# basic-HR20.net
KiCad netlist of a schematic drawn in EAGLE
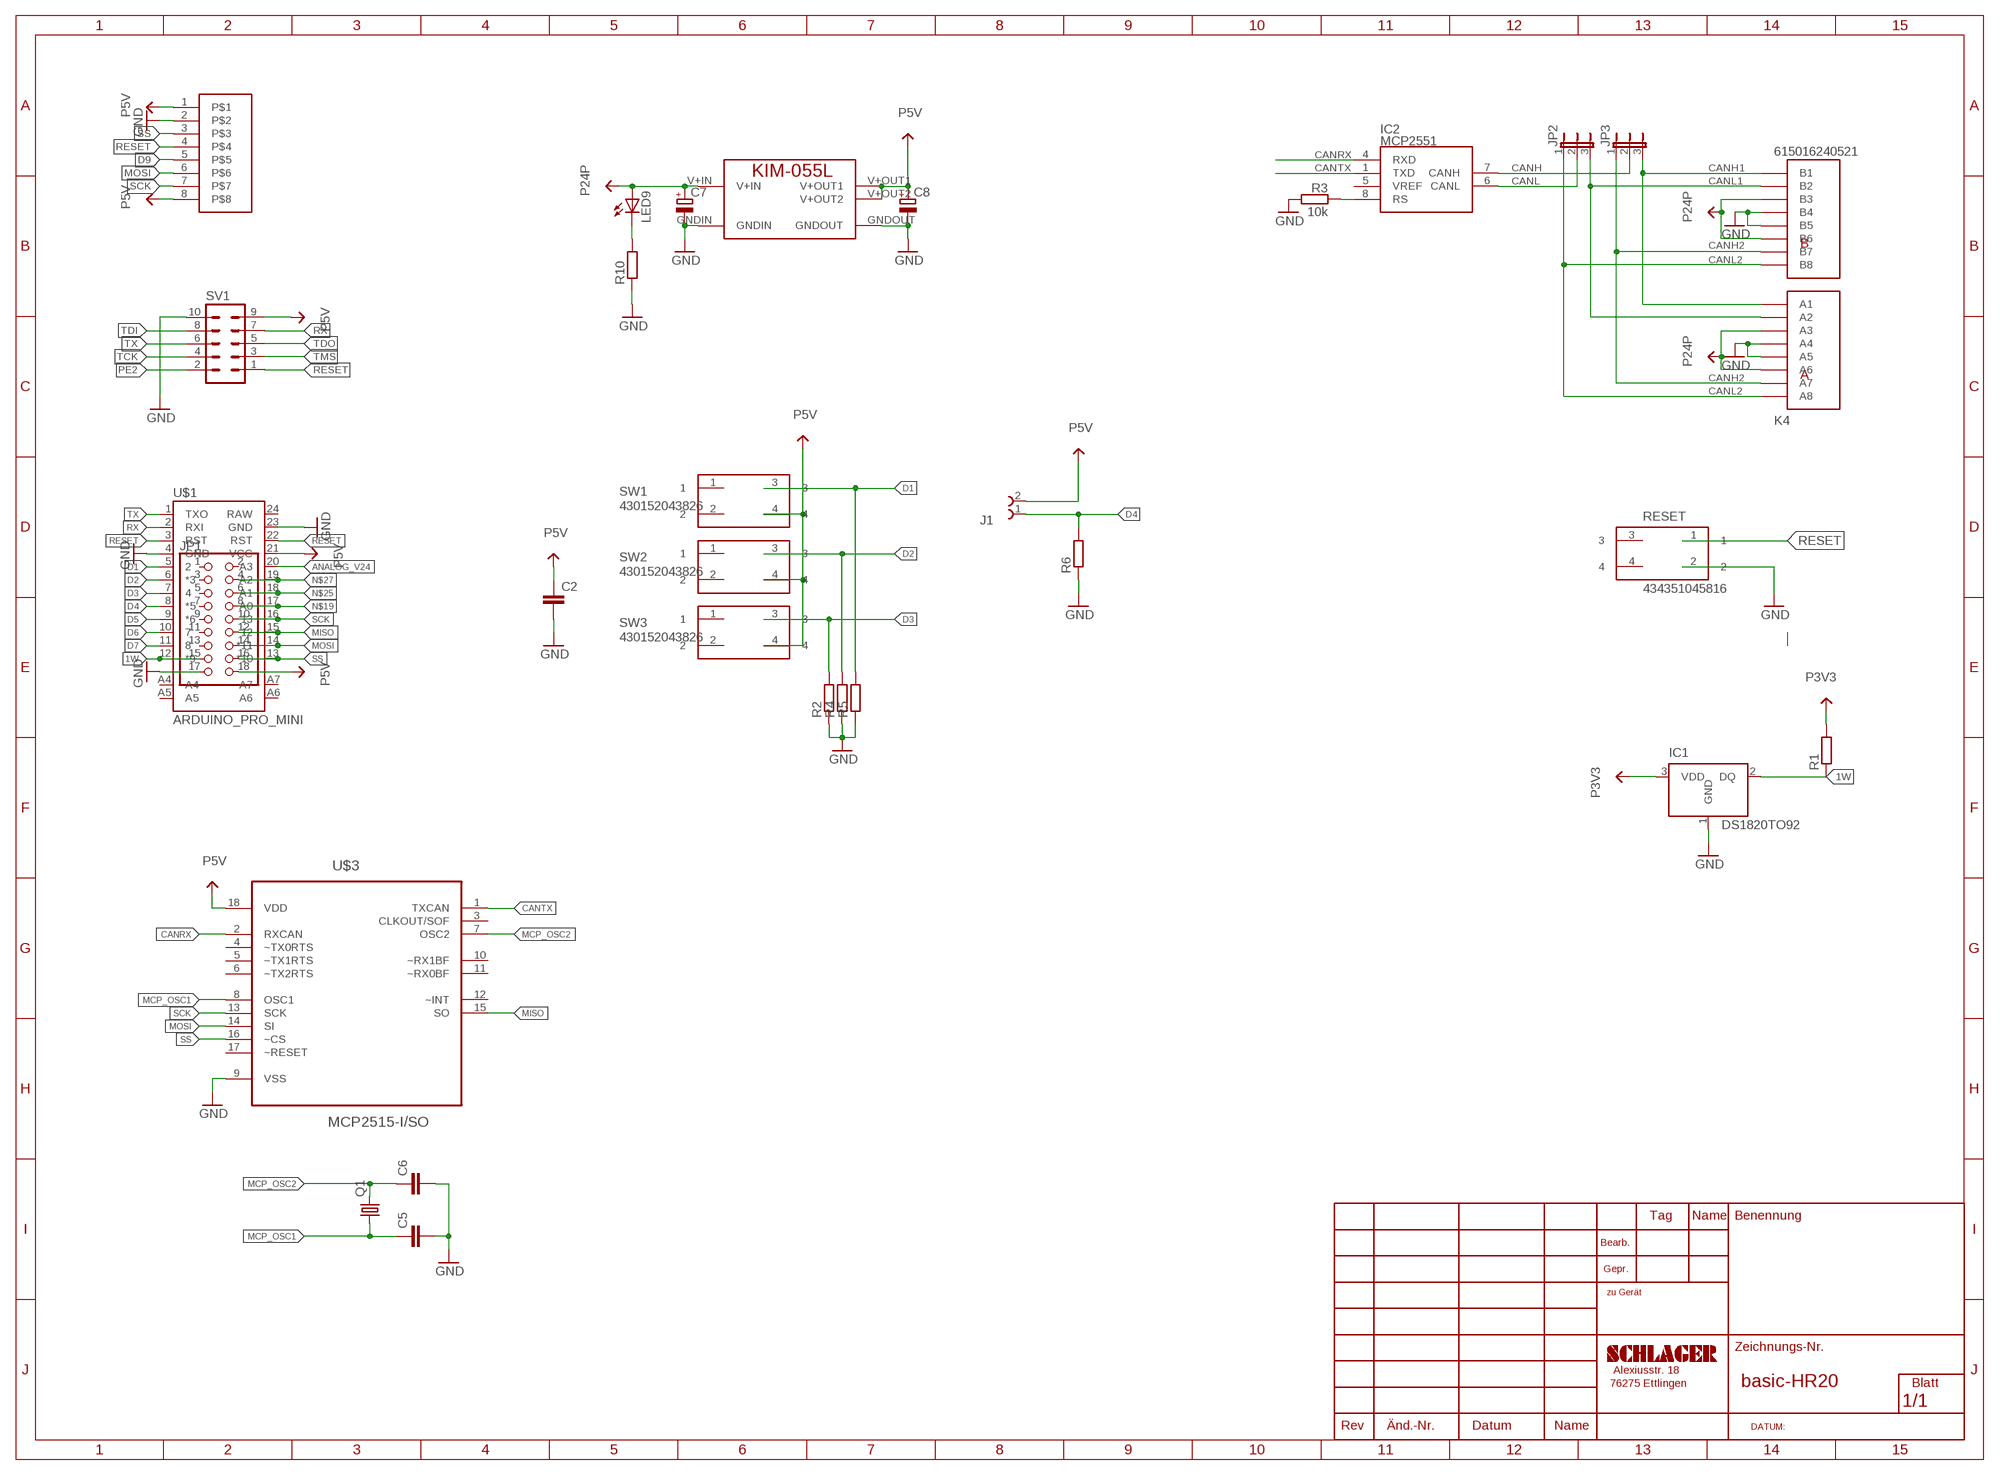
[diagram p0: schematic, sheet 1]

(export (version "E")
  (design (tool "Eeschema 10.0.6"))
  (components
    (comp (ref "C2")
      (value "C-EUC0805")
      (footprint "eagle-import:C0805")
      (libsource (lib "eagle-import") (part "C-EUC0805"))
    )
    (comp (ref "C5")
      (value "C-EUC0805")
      (footprint "eagle-import:C0805")
      (libsource (lib "eagle-import") (part "C-EUC0805"))
    )
    (comp (ref "C6")
      (value "C-EUC0805")
      (footprint "eagle-import:C0805")
      (libsource (lib "eagle-import") (part "C-EUC0805"))
    )
    (comp (ref "C7")
      (value "CPOL-EUE5-10.5")
      (footprint "eagle-import:E5-10,5")
      (libsource (lib "eagle-import") (part "CPOL-EUE5-10.5"))
    )
    (comp (ref "C8")
      (value "CPOL-EUE5-10.5")
      (footprint "eagle-import:E5-10,5")
      (libsource (lib "eagle-import") (part "CPOL-EUE5-10.5"))
    )
    (comp (ref "IC1")
      (value "DS1820TO92")
      (footprint "eagle-import:TO-92")
      (libsource (lib "eagle-import") (part "DS1820TO92"))
    )
    (comp (ref "IC2")
      (value "MCP2551")
      (footprint "eagle-import:SO-8")
      (libsource (lib "eagle-import") (part "MCP2551"))
    )
    (comp (ref "J1")
      (value "691312510002")
      (footprint "eagle-import:691312510002")
      (libsource (lib "eagle-import") (part "691312510002"))
    )
    (comp (ref "JP1")
      (value "PINHD-2X9")
      (footprint "eagle-import:2X09")
      (libsource (lib "eagle-import") (part "PINHD-2X9"))
    )
    (comp (ref "JP2")
      (value "JP2E")
      (footprint "eagle-import:JP2")
      (libsource (lib "eagle-import") (part "JP2E"))
    )
    (comp (ref "JP3")
      (value "JP2E")
      (footprint "eagle-import:JP2")
      (libsource (lib "eagle-import") (part "JP2E"))
    )
    (comp (ref "K4")
      (value "615016240521")
      (footprint "eagle-import:615016240521")
      (libsource (lib "eagle-import") (part "615016240521"))
    )
    (comp (ref "LED9")
      (value "LED3MM")
      (footprint "eagle-import:LED3MM")
      (libsource (lib "eagle-import") (part "LED3MM"))
    )
    (comp (ref "MOD1")
      (value "KIM-055L")
      (footprint "eagle-import:KIM-055L")
      (libsource (lib "eagle-import") (part "KIM-055L"))
    )
    (comp (ref "Q1")
      (value "CRYSTALHC49S")
      (footprint "eagle-import:HC49_S")
      (libsource (lib "eagle-import") (part "CRYSTALHC49S"))
    )
    (comp (ref "R1")
      (value "R-EU_M0805")
      (footprint "eagle-import:M0805")
      (libsource (lib "eagle-import") (part "schlager_passiv_R-EU_M0805"))
    )
    (comp (ref "R2")
      (value "R-EU_R0805")
      (footprint "eagle-import:R0805")
      (libsource (lib "eagle-import") (part "schlager_passiv_R-EU_R0805"))
    )
    (comp (ref "R3")
      (value "10k")
      (footprint "eagle-import:R0603")
      (libsource (lib "eagle-import") (part "R-EU_R0603"))
    )
    (comp (ref "R4")
      (value "R-EU_R0805")
      (footprint "eagle-import:R0805")
      (libsource (lib "eagle-import") (part "schlager_passiv_R-EU_R0805"))
    )
    (comp (ref "R5")
      (value "R-EU_R0805")
      (footprint "eagle-import:R0805")
      (libsource (lib "eagle-import") (part "schlager_passiv_R-EU_R0805"))
    )
    (comp (ref "R6")
      (value "R-EU_R0805")
      (footprint "eagle-import:R0805")
      (libsource (lib "eagle-import") (part "schlager_passiv_R-EU_R0805"))
    )
    (comp (ref "R10")
      (value "R-EU_R0805")
      (footprint "eagle-import:R0805")
      (libsource (lib "eagle-import") (part "schlager_passiv_R-EU_R0805"))
    )
    (comp (ref "RESET")
      (value "434351045816")
      (footprint "eagle-import:434351045816")
      (libsource (lib "eagle-import") (part "434351045816"))
    )
    (comp (ref "SV1")
      (value "ML10")
      (footprint "eagle-import:ML10")
      (libsource (lib "eagle-import") (part "ML10"))
    )
    (comp (ref "SW1")
      (value "430152043826")
      (footprint "eagle-import:430152043826")
      (libsource (lib "eagle-import") (part "430152043826"))
    )
    (comp (ref "SW2")
      (value "430152043826")
      (footprint "eagle-import:430152043826")
      (libsource (lib "eagle-import") (part "430152043826"))
    )
    (comp (ref "SW3")
      (value "430152043826")
      (footprint "eagle-import:430152043826")
      (libsource (lib "eagle-import") (part "430152043826"))
    )
    (comp (ref "U$1")
      (value "ARDUINO_PRO_MINI")
      (footprint "eagle-import:ARDUINO_PRO_MINI")
      (libsource (lib "eagle-import") (part "ARDUINO_PRO_MINI"))
    )
    (comp (ref "U$2")
      (value "1.44-128X128")
      (footprint "eagle-import:1.44-128X128")
      (libsource (lib "eagle-import") (part "1.44-128X128"))
    )
    (comp (ref "U$3")
      (value "MCP2515-I/SO")
      (footprint "eagle-import:SOIC127P1034X264-18N")
      (libsource (lib "eagle-import") (part "MCP2515-I/SO"))
    )
  )
  (nets
    (net (code "1") (name "/CANH") (class "Default")
      (node (ref "IC2") (pin "7") (pinfunction "CANH_7") (pintype "bidirectional"))
      (node (ref "JP3") (pin "2") (pinfunction "2_2") (pintype "passive"))
    )
    (net (code "2") (name "/CANH1") (class "Default")
      (node (ref "JP3") (pin "3") (pinfunction "3_3") (pintype "passive"))
      (node (ref "K4") (pin "A1") (pinfunction "A1_A1") (pintype "passive"))
      (node (ref "K4") (pin "B1") (pinfunction "B1_B1") (pintype "passive"))
    )
    (net (code "3") (name "/CANH2") (class "Default")
      (node (ref "JP3") (pin "1") (pinfunction "1_1") (pintype "passive"))
      (node (ref "K4") (pin "A7") (pinfunction "A7_A7") (pintype "passive"))
      (node (ref "K4") (pin "B7") (pinfunction "B7_B7") (pintype "passive"))
    )
    (net (code "4") (name "/CANL") (class "Default")
      (node (ref "IC2") (pin "6") (pinfunction "CANL_6") (pintype "bidirectional"))
      (node (ref "JP2") (pin "2") (pinfunction "2_2") (pintype "passive"))
    )
    (net (code "5") (name "/CANL1") (class "Default")
      (node (ref "JP2") (pin "3") (pinfunction "3_3") (pintype "passive"))
      (node (ref "K4") (pin "A2") (pinfunction "A2_A2") (pintype "passive"))
      (node (ref "K4") (pin "B2") (pinfunction "B2_B2") (pintype "passive"))
    )
    (net (code "6") (name "/CANL2") (class "Default")
      (node (ref "JP2") (pin "1") (pinfunction "1_1") (pintype "passive"))
      (node (ref "K4") (pin "A8") (pinfunction "A8_A8") (pintype "passive"))
      (node (ref "K4") (pin "B8") (pinfunction "B8_B8") (pintype "passive"))
    )
    (net (code "7") (name "1W") (class "Default")
      (node (ref "IC1") (pin "2") (pinfunction "DQ_2") (pintype "output"))
      (node (ref "JP1") (pin "15") (pinfunction "15_15") (pintype "passive"))
      (node (ref "R1") (pin "1") (pinfunction "1_1") (pintype "passive"))
      (node (ref "U$1") (pin "12") (pinfunction "*9_12") (pintype "bidirectional"))
    )
    (net (code "8") (name "ANALOG_V24") (class "Default")
      (node (ref "U$1") (pin "20") (pinfunction "A3_20") (pintype "bidirectional"))
    )
    (net (code "9") (name "CANRX") (class "Default")
      (node (ref "IC2") (pin "4") (pinfunction "RXD_4") (pintype "bidirectional"))
      (node (ref "U$3") (pin "2") (pinfunction "RXCAN_2") (pintype "input"))
    )
    (net (code "10") (name "CANTX") (class "Default")
      (node (ref "IC2") (pin "1") (pinfunction "TXD_1") (pintype "bidirectional"))
      (node (ref "U$3") (pin "1") (pinfunction "TXCAN_1") (pintype "output"))
    )
    (net (code "11") (name "D1") (class "Default")
      (node (ref "R5") (pin "2") (pinfunction "2_2") (pintype "passive"))
      (node (ref "SW1") (pin "3") (pinfunction "3_3") (pintype "bidirectional"))
      (node (ref "U$1") (pin "5") (pinfunction "2_5") (pintype "bidirectional"))
    )
    (net (code "12") (name "D2") (class "Default")
      (node (ref "R4") (pin "2") (pinfunction "2_2") (pintype "passive"))
      (node (ref "SW2") (pin "3") (pinfunction "3_3") (pintype "bidirectional"))
      (node (ref "U$1") (pin "6") (pinfunction "*3_6") (pintype "bidirectional"))
    )
    (net (code "13") (name "D3") (class "Default")
      (node (ref "R2") (pin "2") (pinfunction "2_2") (pintype "passive"))
      (node (ref "SW3") (pin "3") (pinfunction "3_3") (pintype "bidirectional"))
      (node (ref "U$1") (pin "7") (pinfunction "4_7") (pintype "bidirectional"))
    )
    (net (code "14") (name "D4") (class "Default")
      (node (ref "J1") (pin "1") (pinfunction "1_1") (pintype "passive"))
      (node (ref "R6") (pin "2") (pinfunction "2_2") (pintype "passive"))
      (node (ref "U$1") (pin "8") (pinfunction "*5_8") (pintype "bidirectional"))
    )
    (net (code "15") (name "D5") (class "Default")
      (node (ref "U$1") (pin "9") (pinfunction "*6_9") (pintype "bidirectional"))
    )
    (net (code "16") (name "D6") (class "Default")
      (node (ref "U$1") (pin "10") (pinfunction "7_10") (pintype "bidirectional"))
    )
    (net (code "17") (name "D7") (class "Default")
      (node (ref "U$1") (pin "11") (pinfunction "8_11") (pintype "bidirectional"))
    )
    (net (code "18") (name "D9") (class "Default")
      (node (ref "U$2") (pin "5") (pinfunction "P$5_5") (pintype "bidirectional"))
    )
    (net (code "19") (name "GND") (class "Default")
      (node (ref "C2") (pin "2") (pinfunction "2_2") (pintype "passive"))
      (node (ref "C5") (pin "2") (pinfunction "2_2") (pintype "passive"))
      (node (ref "C6") (pin "2") (pinfunction "2_2") (pintype "passive"))
      (node (ref "C7") (pin "-") (pinfunction "-_-") (pintype "passive"))
      (node (ref "C8") (pin "-") (pinfunction "-_-") (pintype "passive"))
      (node (ref "IC1") (pin "1") (pinfunction "GND_1") (pintype "power_in"))
      (node (ref "JP1") (pin "17") (pinfunction "17_17") (pintype "passive"))
      (node (ref "K4") (pin "A4") (pinfunction "A4_A4") (pintype "passive"))
      (node (ref "K4") (pin "A5") (pinfunction "A5_A5") (pintype "passive"))
      (node (ref "K4") (pin "B4") (pinfunction "B4_B4") (pintype "passive"))
      (node (ref "K4") (pin "B5") (pinfunction "B5_B5") (pintype "passive"))
      (node (ref "MOD1") (pin "GNDIN") (pinfunction "GNDIN_GNDIN") (pintype "bidirectional"))
      (node (ref "MOD1") (pin "GNDOUT") (pinfunction "GNDOUT_GNDOUT") (pintype "bidirectional"))
      (node (ref "R10") (pin "1") (pinfunction "1_1") (pintype "passive"))
      (node (ref "R2") (pin "1") (pinfunction "1_1") (pintype "passive"))
      (node (ref "R3") (pin "2") (pinfunction "2_2") (pintype "passive"))
      (node (ref "R4") (pin "1") (pinfunction "1_1") (pintype "passive"))
      (node (ref "R5") (pin "1") (pinfunction "1_1") (pintype "passive"))
      (node (ref "R6") (pin "1") (pinfunction "1_1") (pintype "passive"))
      (node (ref "RESET") (pin "2") (pinfunction "2_2") (pintype "bidirectional"))
      (node (ref "SV1") (pin "10") (pinfunction "10_10") (pintype "passive"))
      (node (ref "U$1") (pin "23") (pinfunction "GND_23") (pintype "bidirectional"))
      (node (ref "U$1") (pin "4") (pinfunction "GND_4") (pintype "bidirectional"))
      (node (ref "U$2") (pin "2") (pinfunction "P$2_2") (pintype "bidirectional"))
      (node (ref "U$3") (pin "9") (pinfunction "VSS_9") (pintype "power_in"))
    )
    (net (code "20") (name "MCP_OSC1") (class "Default")
      (node (ref "C5") (pin "1") (pinfunction "1_1") (pintype "passive"))
      (node (ref "Q1") (pin "1") (pinfunction "1_1") (pintype "passive"))
      (node (ref "U$3") (pin "8") (pinfunction "OSC1_8") (pintype "input"))
    )
    (net (code "21") (name "MCP_OSC2") (class "Default")
      (node (ref "C6") (pin "1") (pinfunction "1_1") (pintype "passive"))
      (node (ref "Q1") (pin "2") (pinfunction "2_2") (pintype "passive"))
      (node (ref "U$3") (pin "7") (pinfunction "OSC2_7") (pintype "output"))
    )
    (net (code "22") (name "MISO") (class "Default")
      (node (ref "JP1") (pin "12") (pinfunction "12_12") (pintype "passive"))
      (node (ref "U$1") (pin "15") (pinfunction "12_15") (pintype "bidirectional"))
      (node (ref "U$3") (pin "15") (pinfunction "SO_15") (pintype "output"))
    )
    (net (code "23") (name "MOSI") (class "Default")
      (node (ref "JP1") (pin "14") (pinfunction "14_14") (pintype "passive"))
      (node (ref "U$1") (pin "14") (pinfunction "*11_14") (pintype "bidirectional"))
      (node (ref "U$2") (pin "6") (pinfunction "P$6_6") (pintype "bidirectional"))
      (node (ref "U$3") (pin "14") (pinfunction "SI_14") (pintype "input"))
    )
    (net (code "24") (name "N$19") (class "Default")
      (node (ref "JP1") (pin "8") (pinfunction "8_8") (pintype "passive"))
      (node (ref "U$1") (pin "17") (pinfunction "A0_17") (pintype "bidirectional"))
    )
    (net (code "25") (name "N$25") (class "Default")
      (node (ref "JP1") (pin "6") (pinfunction "6_6") (pintype "passive"))
      (node (ref "U$1") (pin "18") (pinfunction "A1_18") (pintype "bidirectional"))
    )
    (net (code "26") (name "N$27") (class "Default")
      (node (ref "JP1") (pin "4") (pinfunction "4_4") (pintype "passive"))
      (node (ref "U$1") (pin "19") (pinfunction "A2_19") (pintype "bidirectional"))
    )
    (net (code "27") (name "Net-(IC2A-RS)") (class "Default")
      (node (ref "IC2") (pin "8") (pinfunction "RS_8") (pintype "bidirectional"))
      (node (ref "R3") (pin "1") (pinfunction "1_1") (pintype "passive"))
    )
    (net (code "28") (name "Net-(LED9-C)") (class "Default")
      (node (ref "LED9") (pin "K") (pinfunction "C_K") (pintype "passive"))
      (node (ref "R10") (pin "2") (pinfunction "2_2") (pintype "passive"))
    )
    (net (code "29") (name "P3V3") (class "Default")
      (node (ref "IC1") (pin "3") (pinfunction "VDD_3") (pintype "input"))
      (node (ref "R1") (pin "2") (pinfunction "2_2") (pintype "passive"))
    )
    (net (code "30") (name "P5V") (class "Default")
      (node (ref "C2") (pin "1") (pinfunction "1_1") (pintype "passive"))
      (node (ref "C8") (pin "+") (pinfunction "+_+") (pintype "passive"))
      (node (ref "J1") (pin "2") (pinfunction "2_2") (pintype "passive"))
      (node (ref "JP1") (pin "18") (pinfunction "18_18") (pintype "passive"))
      (node (ref "MOD1") (pin "V+OUT1") (pinfunction "V+OUT1_V+OUT1") (pintype "bidirectional"))
      (node (ref "MOD1") (pin "V+OUT2") (pinfunction "V+OUT2_V+OUT2") (pintype "bidirectional"))
      (node (ref "SV1") (pin "9") (pinfunction "9_9") (pintype "passive"))
      (node (ref "SW1") (pin "4") (pinfunction "4_4") (pintype "bidirectional"))
      (node (ref "SW2") (pin "4") (pinfunction "4_4") (pintype "bidirectional"))
      (node (ref "SW3") (pin "4") (pinfunction "4_4") (pintype "bidirectional"))
      (node (ref "U$1") (pin "21") (pinfunction "VCC_21") (pintype "bidirectional"))
      (node (ref "U$2") (pin "1") (pinfunction "P$1_1") (pintype "bidirectional"))
      (node (ref "U$2") (pin "8") (pinfunction "P$8_8") (pintype "bidirectional"))
      (node (ref "U$3") (pin "18") (pinfunction "VDD_18") (pintype "power_in"))
    )
    (net (code "31") (name "P24P") (class "Default")
      (node (ref "C7") (pin "+") (pinfunction "+_+") (pintype "passive"))
      (node (ref "K4") (pin "A3") (pinfunction "A3_A3") (pintype "passive"))
      (node (ref "K4") (pin "A6") (pinfunction "A6_A6") (pintype "passive"))
      (node (ref "K4") (pin "B3") (pinfunction "B3_B3") (pintype "passive"))
      (node (ref "K4") (pin "B6") (pinfunction "B6_B6") (pintype "passive"))
      (node (ref "LED9") (pin "A") (pinfunction "A_A") (pintype "passive"))
      (node (ref "MOD1") (pin "V+IN") (pinfunction "V+IN_V+IN") (pintype "bidirectional"))
    )
    (net (code "32") (name "PE2") (class "Default")
      (node (ref "SV1") (pin "2") (pinfunction "2_2") (pintype "passive"))
    )
    (net (code "33") (name "RESET") (class "Default")
      (node (ref "RESET") (pin "1") (pinfunction "1_1") (pintype "bidirectional"))
      (node (ref "SV1") (pin "1") (pinfunction "1_1") (pintype "passive"))
      (node (ref "U$1") (pin "22") (pinfunction "RST_22") (pintype "bidirectional"))
      (node (ref "U$1") (pin "3") (pinfunction "RST_3") (pintype "bidirectional"))
      (node (ref "U$2") (pin "4") (pinfunction "P$4_4") (pintype "bidirectional"))
    )
    (net (code "34") (name "RX") (class "Default")
      (node (ref "SV1") (pin "7") (pinfunction "7_7") (pintype "passive"))
      (node (ref "U$1") (pin "2") (pinfunction "RXI_2") (pintype "bidirectional"))
    )
    (net (code "35") (name "SCK") (class "Default")
      (node (ref "JP1") (pin "10") (pinfunction "10_10") (pintype "passive"))
      (node (ref "U$1") (pin "16") (pinfunction "13_16") (pintype "bidirectional"))
      (node (ref "U$2") (pin "7") (pinfunction "P$7_7") (pintype "bidirectional"))
      (node (ref "U$3") (pin "13") (pinfunction "SCK_13") (pintype "input"))
    )
    (net (code "36") (name "SS") (class "Default")
      (node (ref "JP1") (pin "16") (pinfunction "16_16") (pintype "passive"))
      (node (ref "U$1") (pin "13") (pinfunction "*10_13") (pintype "bidirectional"))
      (node (ref "U$2") (pin "3") (pinfunction "P$3_3") (pintype "bidirectional"))
      (node (ref "U$3") (pin "16") (pinfunction "~{CS}_16") (pintype "input"))
    )
    (net (code "37") (name "TCK") (class "Default")
      (node (ref "SV1") (pin "4") (pinfunction "4_4") (pintype "passive"))
    )
    (net (code "38") (name "TDI") (class "Default")
      (node (ref "SV1") (pin "8") (pinfunction "8_8") (pintype "passive"))
    )
    (net (code "39") (name "TDO") (class "Default")
      (node (ref "SV1") (pin "5") (pinfunction "5_5") (pintype "passive"))
    )
    (net (code "40") (name "TMS") (class "Default")
      (node (ref "SV1") (pin "3") (pinfunction "3_3") (pintype "passive"))
    )
    (net (code "41") (name "TX") (class "Default")
      (node (ref "SV1") (pin "6") (pinfunction "6_6") (pintype "passive"))
      (node (ref "U$1") (pin "1") (pinfunction "TXO_1") (pintype "bidirectional"))
    )
    (net (code "42") (name "unconnected-(IC2A-VREF-Pad5)") (class "Default")
      (node (ref "IC2") (pin "5") (pinfunction "VREF_5") (pintype "bidirectional"))
    )
    (net (code "43") (name "unconnected-(JP1-Pad1)") (class "Default")
      (node (ref "JP1") (pin "1") (pinfunction "1_1") (pintype "passive"))
    )
    (net (code "44") (name "unconnected-(JP1-Pad2)") (class "Default")
      (node (ref "JP1") (pin "2") (pinfunction "2_2") (pintype "passive"))
    )
    (net (code "45") (name "unconnected-(JP1-Pad3)") (class "Default")
      (node (ref "JP1") (pin "3") (pinfunction "3_3") (pintype "passive"))
    )
    (net (code "46") (name "unconnected-(JP1-Pad5)") (class "Default")
      (node (ref "JP1") (pin "5") (pinfunction "5_5") (pintype "passive"))
    )
    (net (code "47") (name "unconnected-(JP1-Pad7)") (class "Default")
      (node (ref "JP1") (pin "7") (pinfunction "7_7") (pintype "passive"))
    )
    (net (code "48") (name "unconnected-(JP1-Pad9)") (class "Default")
      (node (ref "JP1") (pin "9") (pinfunction "9_9") (pintype "passive"))
    )
    (net (code "49") (name "unconnected-(JP1-Pad11)") (class "Default")
      (node (ref "JP1") (pin "11") (pinfunction "11_11") (pintype "passive"))
    )
    (net (code "50") (name "unconnected-(JP1-Pad13)") (class "Default")
      (node (ref "JP1") (pin "13") (pinfunction "13_13") (pintype "passive"))
    )
    (net (code "51") (name "unconnected-(RESET-Pad3)") (class "Default")
      (node (ref "RESET") (pin "3") (pinfunction "3_3") (pintype "bidirectional"))
    )
    (net (code "52") (name "unconnected-(RESET-Pad4)") (class "Default")
      (node (ref "RESET") (pin "4") (pinfunction "4_4") (pintype "bidirectional"))
    )
    (net (code "53") (name "unconnected-(SW1-Pad1)") (class "Default")
      (node (ref "SW1") (pin "1") (pinfunction "1_1") (pintype "bidirectional"))
    )
    (net (code "54") (name "unconnected-(SW1-Pad2)") (class "Default")
      (node (ref "SW1") (pin "2") (pinfunction "2_2") (pintype "bidirectional"))
    )
    (net (code "55") (name "unconnected-(SW2-Pad1)") (class "Default")
      (node (ref "SW2") (pin "1") (pinfunction "1_1") (pintype "bidirectional"))
    )
    (net (code "56") (name "unconnected-(SW2-Pad2)") (class "Default")
      (node (ref "SW2") (pin "2") (pinfunction "2_2") (pintype "bidirectional"))
    )
    (net (code "57") (name "unconnected-(SW3-Pad1)") (class "Default")
      (node (ref "SW3") (pin "1") (pinfunction "1_1") (pintype "bidirectional"))
    )
    (net (code "58") (name "unconnected-(SW3-Pad2)") (class "Default")
      (node (ref "SW3") (pin "2") (pinfunction "2_2") (pintype "bidirectional"))
    )
    (net (code "59") (name "unconnected-(U$1-PadA4)") (class "Default")
      (node (ref "U$1") (pin "A4") (pinfunction "A4_A4") (pintype "bidirectional"))
    )
    (net (code "60") (name "unconnected-(U$1-PadA5)") (class "Default")
      (node (ref "U$1") (pin "A5") (pinfunction "A5_A5") (pintype "bidirectional"))
    )
    (net (code "61") (name "unconnected-(U$1-PadA6)") (class "Default")
      (node (ref "U$1") (pin "A6") (pinfunction "A6_A6") (pintype "bidirectional"))
    )
    (net (code "62") (name "unconnected-(U$1-PadA7)") (class "Default")
      (node (ref "U$1") (pin "A7") (pinfunction "A7_A7") (pintype "bidirectional"))
    )
    (net (code "63") (name "unconnected-(U$1-RAW-Pad24)") (class "Default")
      (node (ref "U$1") (pin "24") (pinfunction "RAW_24") (pintype "bidirectional"))
    )
    (net (code "64") (name "unconnected-(U$3-CLKOUT{slash}SOF-Pad3)") (class "Default")
      (node (ref "U$3") (pin "3") (pinfunction "CLKOUT/SOF_3") (pintype "output"))
    )
    (net (code "65") (name "unconnected-(U$3-~{INT}-Pad12)") (class "Default")
      (node (ref "U$3") (pin "12") (pinfunction "~{INT}_12") (pintype "output"))
    )
    (net (code "66") (name "unconnected-(U$3-~{RESET}-Pad17)") (class "Default")
      (node (ref "U$3") (pin "17") (pinfunction "~{RESET}_17") (pintype "input"))
    )
    (net (code "67") (name "unconnected-(U$3-~{RX0BF}-Pad11)") (class "Default")
      (node (ref "U$3") (pin "11") (pinfunction "~{RX0BF}_11") (pintype "output"))
    )
    (net (code "68") (name "unconnected-(U$3-~{RX1BF}-Pad10)") (class "Default")
      (node (ref "U$3") (pin "10") (pinfunction "~{RX1BF}_10") (pintype "output"))
    )
    (net (code "69") (name "unconnected-(U$3-~{TX0RTS}-Pad4)") (class "Default")
      (node (ref "U$3") (pin "4") (pinfunction "~{TX0RTS}_4") (pintype "input"))
    )
    (net (code "70") (name "unconnected-(U$3-~{TX1RTS}-Pad5)") (class "Default")
      (node (ref "U$3") (pin "5") (pinfunction "~{TX1RTS}_5") (pintype "input"))
    )
    (net (code "71") (name "unconnected-(U$3-~{TX2RTS}-Pad6)") (class "Default")
      (node (ref "U$3") (pin "6") (pinfunction "~{TX2RTS}_6") (pintype "input"))
    )
  )
)
